# BM83.net
KiCad netlist of a schematic drawn in Altium Designer
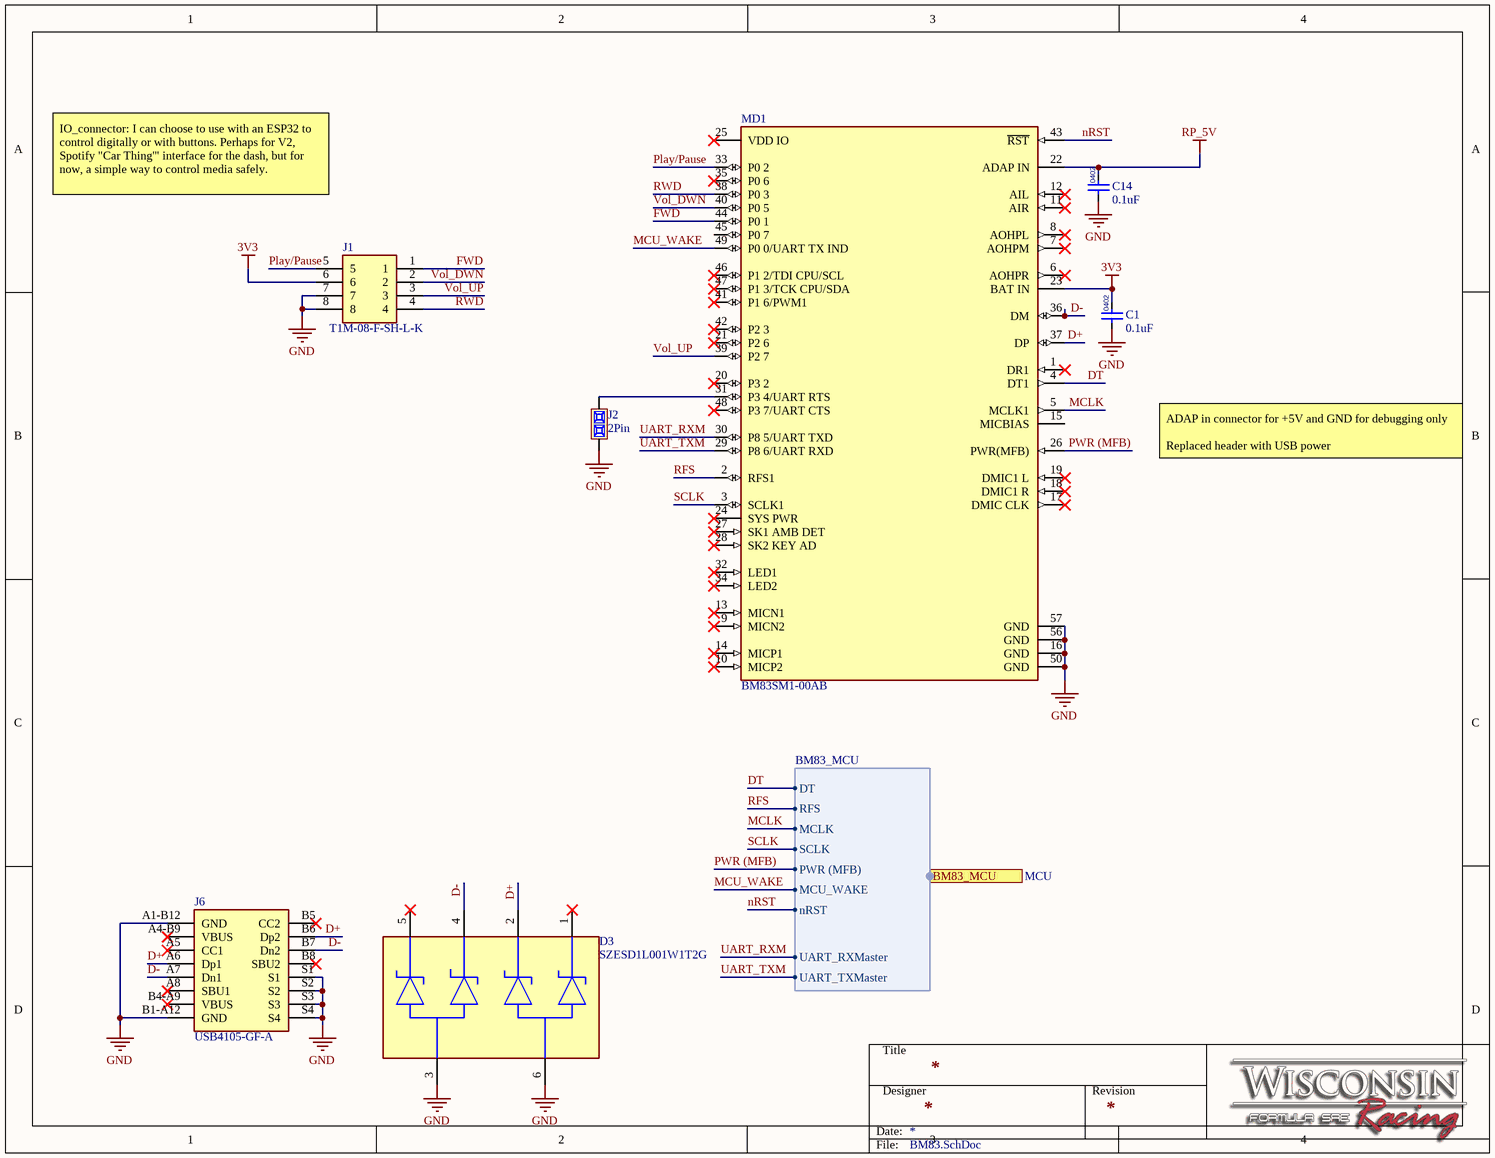
[diagram p0: BM83.SchDoc]

(export (version "E")
  (design (tool "Eeschema 10.0.6"))
  (components
    (comp (ref "C1")
      (value "0.1uF")
      (footprint "FP-CC0402-IPC_B")
      (fields (field (name "TOLERANCE") "10%"))
      (libsource (lib "University of Wisconsin Formula FSAE") (part "0402 ceramic cap"))
    )
    (comp (ref "C14")
      (value "0.1uF")
      (footprint "FP-CC0402-IPC_B")
      (fields (field (name "TOLERANCE") "10%"))
      (libsource (lib "University of Wisconsin Formula FSAE") (part "0402 ceramic cap"))
    )
    (comp (ref "D3")
      (value "SZESD1L001W1T2G")
      (footprint "FP-419B-02-MFG")
      (libsource (lib "Altium Content Vault") (part "f9bd4b2d15702f63c48081affbe3109"))
    )
    (comp (ref "J1")
      (value "T1M-08-F-SH-L-K")
      (footprint "SamacSys:T1M-08-F-SH-L-K")
      (description "Connector")
      (fields (field (name "MOUSER PART NUMBER") "200-T1M08FSHLK"))
      (libsource (lib "*") (part "T1M-08-F-SH-L-K"))
    )
    (comp (ref "J2")
      (value "2Pin")
      (footprint "2 Pin Male")
      (libsource (lib "University of Wisconsin Formula FSAE") (part "2 Pin Male"))
    )
    (comp (ref "J6")
      (value "USB4105-GF-A")
      (footprint "USB4105-GF-A")
      (description "Conn USB 2.0 Type C RCP 24 POS 0.3mm/0.5mm Solder RA SMD 24 Terminal 1 Port T/R")
      (libsource (lib "University of Wisconsin Formula FSAE") (part "USB4105-GF-A"))
    )
    (comp (ref "MD1")
      (value "BM83SM1-00AB")
      (footprint "FP-BM83SM1-00AB-MFG")
      (description "BLUETOOTH AUDIO MODULE")
      (libsource (lib "Altium Content Vault") (part "59273137af04f48cb9dd2df4763d70c"))
    )
  )
  (nets
    (net (code "2") (name "/D+") (class "Default")
      (node (ref "D3") (pin "2") (pinfunction "2_CATHODE_2") (pintype "passive"))
      (node (ref "J6") (pin "A6") (pinfunction "Dp1_A6") (pintype "passive"))
      (node (ref "J6") (pin "B6") (pinfunction "Dp2_B6") (pintype "passive"))
      (node (ref "MD1") (pin "37") (pinfunction "DP_37") (pintype "bidirectional"))
    )
    (net (code "3") (name "/D-") (class "Default")
      (node (ref "D3") (pin "4") (pinfunction "3_CATHODE_4") (pintype "passive"))
      (node (ref "J6") (pin "A7") (pinfunction "Dn1_A7") (pintype "passive"))
      (node (ref "J6") (pin "B7") (pinfunction "Dn2_B7") (pintype "passive"))
      (node (ref "MD1") (pin "36") (pinfunction "DM_36") (pintype "bidirectional"))
    )
    (net (code "4") (name "/DT") (class "Default")
      (node (ref "MD1") (pin "4") (pinfunction "DT1_4") (pintype "output"))
    )
    (net (code "5") (name "/FWD") (class "Default")
      (node (ref "J1") (pin "1") (pinfunction "1_1") (pintype "passive"))
      (node (ref "MD1") (pin "44") (pinfunction "P0_1_44") (pintype "bidirectional"))
    )
    (net (code "6") (name "/MCLK") (class "Default")
      (node (ref "MD1") (pin "5") (pinfunction "MCLK1_5") (pintype "output"))
    )
    (net (code "7") (name "/MCU_WAKE") (class "Default")
      (node (ref "MD1") (pin "49") (pinfunction "P0_0/UART_TX_IND_49") (pintype "bidirectional"))
    )
    (net (code "8") (name "/PWR (MFB)") (class "Default")
      (node (ref "MD1") (pin "26") (pinfunction "PWR(MFB)_26") (pintype "input"))
    )
    (net (code "9") (name "/Play{slash}Pause") (class "Default")
      (node (ref "J1") (pin "5") (pinfunction "5_5") (pintype "passive"))
      (node (ref "MD1") (pin "33") (pinfunction "P0_2_33") (pintype "bidirectional"))
    )
    (net (code "10") (name "/RFS") (class "Default")
      (node (ref "MD1") (pin "2") (pinfunction "RFS1_2") (pintype "bidirectional"))
    )
    (net (code "11") (name "/RWD") (class "Default")
      (node (ref "J1") (pin "4") (pinfunction "4_4") (pintype "passive"))
      (node (ref "MD1") (pin "38") (pinfunction "P0_3_38") (pintype "bidirectional"))
    )
    (net (code "12") (name "/SCLK") (class "Default")
      (node (ref "MD1") (pin "3") (pinfunction "SCLK1_3") (pintype "bidirectional"))
    )
    (net (code "13") (name "/UART_RXM") (class "Default")
      (node (ref "MD1") (pin "30") (pinfunction "P8_5/UART_TXD_30") (pintype "bidirectional"))
    )
    (net (code "14") (name "/UART_TXM") (class "Default")
      (node (ref "MD1") (pin "29") (pinfunction "P8_6/UART_RXD_29") (pintype "bidirectional"))
    )
    (net (code "15") (name "/Vol_DWN") (class "Default")
      (node (ref "J1") (pin "2") (pinfunction "2_2") (pintype "passive"))
      (node (ref "MD1") (pin "40") (pinfunction "P0_5_40") (pintype "bidirectional"))
    )
    (net (code "16") (name "/Vol_UP") (class "Default")
      (node (ref "J1") (pin "3") (pinfunction "3_3") (pintype "passive"))
      (node (ref "MD1") (pin "39") (pinfunction "P2_7_39") (pintype "bidirectional"))
    )
    (net (code "17") (name "/nRST") (class "Default")
      (node (ref "MD1") (pin "43") (pinfunction "~{RST}_43") (pintype "input"))
    )
    (net (code "19") (name "3V3") (class "Default")
      (node (ref "C1") (pin "2") (pinfunction "2_2") (pintype "passive"))
      (node (ref "J1") (pin "6") (pinfunction "6_6") (pintype "passive"))
      (node (ref "MD1") (pin "23") (pinfunction "BAT_IN_23") (pintype "power_in"))
    )
    (net (code "20") (name "GND") (class "Default")
      (node (ref "C1") (pin "1") (pinfunction "1_1") (pintype "passive"))
      (node (ref "C14") (pin "1") (pinfunction "1_1") (pintype "passive"))
      (node (ref "D3") (pin "3") (pinfunction "GND_3") (pintype "power_in"))
      (node (ref "D3") (pin "6") (pinfunction "GND_6") (pintype "power_in"))
      (node (ref "J1") (pin "7") (pinfunction "7_7") (pintype "passive"))
      (node (ref "J1") (pin "8") (pinfunction "8_8") (pintype "passive"))
      (node (ref "J2") (pin "1") (pinfunction "1_1") (pintype "passive"))
      (node (ref "J6") (pin "A1-B12") (pinfunction "GND_A1-B12") (pintype "passive"))
      (node (ref "J6") (pin "B1-A12") (pinfunction "GND_B1-A12") (pintype "passive"))
      (node (ref "J6") (pin "S1") (pinfunction "S1_S1") (pintype "passive"))
      (node (ref "J6") (pin "S2") (pinfunction "S2_S2") (pintype "passive"))
      (node (ref "J6") (pin "S3") (pinfunction "S3_S3") (pintype "passive"))
      (node (ref "J6") (pin "S4") (pinfunction "S4_S4") (pintype "passive"))
      (node (ref "MD1") (pin "16") (pinfunction "GND_16") (pintype "power_in"))
      (node (ref "MD1") (pin "50") (pinfunction "GND_50") (pintype "power_in"))
      (node (ref "MD1") (pin "56") (pinfunction "GND_56") (pintype "power_in"))
      (node (ref "MD1") (pin "57") (pinfunction "GND_57") (pintype "power_in"))
    )
    (net (code "21") (name "Net-(MD1-P3_4{slash}UART_RTS)") (class "Default")
      (node (ref "J2") (pin "2") (pinfunction "2_2") (pintype "passive"))
      (node (ref "MD1") (pin "31") (pinfunction "P3_4/UART_RTS_31") (pintype "bidirectional"))
    )
    (net (code "22") (name "RP_5V") (class "Default")
      (node (ref "C14") (pin "2") (pinfunction "2_2") (pintype "passive"))
      (node (ref "MD1") (pin "22") (pinfunction "ADAP_IN_22") (pintype "power_in"))
    )
    (net (code "23") (name "unconnected-(D3-1_CATHODE-Pad1)") (class "Default")
      (node (ref "D3") (pin "1") (pinfunction "1_CATHODE_1") (pintype "passive+no_connect"))
    )
    (net (code "24") (name "unconnected-(D3-4_CATHODE-Pad5)") (class "Default")
      (node (ref "D3") (pin "5") (pinfunction "4_CATHODE_5") (pintype "passive+no_connect"))
    )
    (net (code "25") (name "unconnected-(J6-CC1-PadA5)") (class "Default")
      (node (ref "J6") (pin "A5") (pinfunction "CC1_A5") (pintype "passive+no_connect"))
    )
    (net (code "26") (name "unconnected-(J6-CC2-PadB5)") (class "Default")
      (node (ref "J6") (pin "B5") (pinfunction "CC2_B5") (pintype "passive+no_connect"))
    )
    (net (code "27") (name "unconnected-(J6-SBU1-PadA8)") (class "Default")
      (node (ref "J6") (pin "A8") (pinfunction "SBU1_A8") (pintype "passive+no_connect"))
    )
    (net (code "28") (name "unconnected-(J6-SBU2-PadB8)") (class "Default")
      (node (ref "J6") (pin "B8") (pinfunction "SBU2_B8") (pintype "passive+no_connect"))
    )
    (net (code "29") (name "unconnected-(J6-VBUS-PadA4-B9)") (class "Default")
      (node (ref "J6") (pin "A4-B9") (pinfunction "VBUS_A4-B9") (pintype "passive+no_connect"))
    )
    (net (code "30") (name "unconnected-(J6-VBUS-PadB4-A9)") (class "Default")
      (node (ref "J6") (pin "B4-A9") (pinfunction "VBUS_B4-A9") (pintype "passive+no_connect"))
    )
    (net (code "31") (name "unconnected-(MD1-AIL-Pad12)") (class "Default")
      (node (ref "MD1") (pin "12") (pinfunction "AIL_12") (pintype "input+no_connect"))
    )
    (net (code "32") (name "unconnected-(MD1-AIR-Pad11)") (class "Default")
      (node (ref "MD1") (pin "11") (pinfunction "AIR_11") (pintype "input+no_connect"))
    )
    (net (code "33") (name "unconnected-(MD1-AOHPL-Pad8)") (class "Default")
      (node (ref "MD1") (pin "8") (pinfunction "AOHPL_8") (pintype "output+no_connect"))
    )
    (net (code "34") (name "unconnected-(MD1-AOHPM-Pad7)") (class "Default")
      (node (ref "MD1") (pin "7") (pinfunction "AOHPM_7") (pintype "output+no_connect"))
    )
    (net (code "35") (name "unconnected-(MD1-AOHPR-Pad6)") (class "Default")
      (node (ref "MD1") (pin "6") (pinfunction "AOHPR_6") (pintype "output+no_connect"))
    )
    (net (code "36") (name "unconnected-(MD1-DMIC1_L-Pad19)") (class "Default")
      (node (ref "MD1") (pin "19") (pinfunction "DMIC1_L_19") (pintype "input+no_connect"))
    )
    (net (code "37") (name "unconnected-(MD1-DMIC1_R-Pad18)") (class "Default")
      (node (ref "MD1") (pin "18") (pinfunction "DMIC1_R_18") (pintype "input+no_connect"))
    )
    (net (code "38") (name "unconnected-(MD1-DMIC_CLK-Pad17)") (class "Default")
      (node (ref "MD1") (pin "17") (pinfunction "DMIC_CLK_17") (pintype "output+no_connect"))
    )
    (net (code "39") (name "unconnected-(MD1-DR1-Pad1)") (class "Default")
      (node (ref "MD1") (pin "1") (pinfunction "DR1_1") (pintype "input+no_connect"))
    )
    (net (code "40") (name "unconnected-(MD1-LED1-Pad32)") (class "Default")
      (node (ref "MD1") (pin "32") (pinfunction "LED1_32") (pintype "input+no_connect"))
    )
    (net (code "41") (name "unconnected-(MD1-LED2-Pad34)") (class "Default")
      (node (ref "MD1") (pin "34") (pinfunction "LED2_34") (pintype "input+no_connect"))
    )
    (net (code "42") (name "unconnected-(MD1-MICBIAS-Pad15)") (class "Default")
      (node (ref "MD1") (pin "15") (pinfunction "MICBIAS_15") (pintype "power_in"))
    )
    (net (code "43") (name "unconnected-(MD1-MICN1-Pad13)") (class "Default")
      (node (ref "MD1") (pin "13") (pinfunction "MICN1_13") (pintype "input+no_connect"))
    )
    (net (code "44") (name "unconnected-(MD1-MICN2-Pad9)") (class "Default")
      (node (ref "MD1") (pin "9") (pinfunction "MICN2_9") (pintype "input+no_connect"))
    )
    (net (code "45") (name "unconnected-(MD1-MICP1-Pad14)") (class "Default")
      (node (ref "MD1") (pin "14") (pinfunction "MICP1_14") (pintype "input+no_connect"))
    )
    (net (code "46") (name "unconnected-(MD1-MICP2-Pad10)") (class "Default")
      (node (ref "MD1") (pin "10") (pinfunction "MICP2_10") (pintype "input+no_connect"))
    )
    (net (code "47") (name "unconnected-(MD1-P0_6-Pad35)") (class "Default")
      (node (ref "MD1") (pin "35") (pinfunction "P0_6_35") (pintype "bidirectional+no_connect"))
    )
    (net (code "48") (name "unconnected-(MD1-P0_7-Pad45)") (class "Default")
      (node (ref "MD1") (pin "45") (pinfunction "P0_7_45") (pintype "bidirectional"))
    )
    (net (code "49") (name "unconnected-(MD1-P1_2{slash}TDI_CPU{slash}SCL-Pad46)") (class "Default")
      (node (ref "MD1") (pin "46") (pinfunction "P1_2/TDI_CPU/SCL_46") (pintype "bidirectional+no_connect"))
    )
    (net (code "50") (name "unconnected-(MD1-P1_3{slash}TCK_CPU{slash}SDA-Pad47)") (class "Default")
      (node (ref "MD1") (pin "47") (pinfunction "P1_3/TCK_CPU/SDA_47") (pintype "bidirectional+no_connect"))
    )
    (net (code "51") (name "unconnected-(MD1-P1_6{slash}PWM1-Pad41)") (class "Default")
      (node (ref "MD1") (pin "41") (pinfunction "P1_6/PWM1_41") (pintype "bidirectional+no_connect"))
    )
    (net (code "52") (name "unconnected-(MD1-P2_3-Pad42)") (class "Default")
      (node (ref "MD1") (pin "42") (pinfunction "P2_3_42") (pintype "bidirectional+no_connect"))
    )
    (net (code "53") (name "unconnected-(MD1-P2_6-Pad21)") (class "Default")
      (node (ref "MD1") (pin "21") (pinfunction "P2_6_21") (pintype "bidirectional+no_connect"))
    )
    (net (code "54") (name "unconnected-(MD1-P3_2-Pad20)") (class "Default")
      (node (ref "MD1") (pin "20") (pinfunction "P3_2_20") (pintype "bidirectional+no_connect"))
    )
    (net (code "55") (name "unconnected-(MD1-P3_7{slash}UART_CTS-Pad48)") (class "Default")
      (node (ref "MD1") (pin "48") (pinfunction "P3_7/UART_CTS_48") (pintype "bidirectional+no_connect"))
    )
    (net (code "56") (name "unconnected-(MD1-SK1_AMB_DET-Pad27)") (class "Default")
      (node (ref "MD1") (pin "27") (pinfunction "SK1_AMB_DET_27") (pintype "input+no_connect"))
    )
    (net (code "57") (name "unconnected-(MD1-SK2_KEY_AD-Pad28)") (class "Default")
      (node (ref "MD1") (pin "28") (pinfunction "SK2_KEY_AD_28") (pintype "input+no_connect"))
    )
    (net (code "58") (name "unconnected-(MD1-SYS_PWR-Pad24)") (class "Default")
      (node (ref "MD1") (pin "24") (pinfunction "SYS_PWR_24") (pintype "power_in+no_connect"))
    )
    (net (code "59") (name "unconnected-(MD1-VDD_IO-Pad25)") (class "Default")
      (node (ref "MD1") (pin "25") (pinfunction "VDD_IO_25") (pintype "power_in+no_connect"))
    )
  )
)
